# Flex-USB.net
KiCad netlist of a schematic drawn in Altium Designer
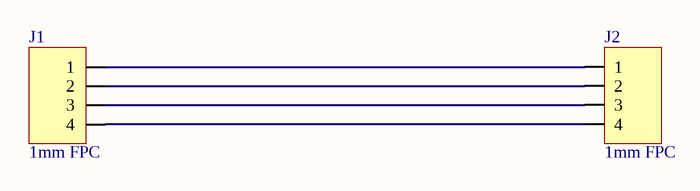
[diagram p0: Flex-USB.SchDoc]

(export (version "E")
  (design (tool "Eeschema 10.0.6"))
  (components
    (comp (ref "J1")
      (value "1mm FPC")
      (footprint "FPC-1mm-4P")
      (description "1mm Pitch 4P FPC")
      (libsource (lib "") (part "FPC-1mm-4P_1"))
    )
    (comp (ref "J2")
      (value "1mm FPC")
      (footprint "FPC-1mm-4P")
      (description "1mm Pitch 4P FPC")
      (libsource (lib "LED-Driver-Library") (part "FPC-1mm-4P"))
    )
  )
  (nets
    (net (code "1") (name "Net-(J1-Pad1)") (class "Default")
      (node (ref "J1") (pin "1") (pinfunction "1_1") (pintype "passive"))
      (node (ref "J2") (pin "1") (pinfunction "1_1") (pintype "passive"))
    )
    (net (code "2") (name "Net-(J1-Pad2)") (class "Default")
      (node (ref "J1") (pin "2") (pinfunction "2_2") (pintype "passive"))
      (node (ref "J2") (pin "2") (pinfunction "2_2") (pintype "passive"))
    )
    (net (code "3") (name "Net-(J1-Pad3)") (class "Default")
      (node (ref "J1") (pin "3") (pinfunction "3_3") (pintype "passive"))
      (node (ref "J2") (pin "3") (pinfunction "3_3") (pintype "passive"))
    )
    (net (code "4") (name "Net-(J1-Pad4)") (class "Default")
      (node (ref "J1") (pin "4") (pinfunction "4_4") (pintype "passive"))
      (node (ref "J2") (pin "4") (pinfunction "4_4") (pintype "passive"))
    )
  )
)
